# msp430f5528.net
KiCad netlist of a schematic drawn in EAGLE
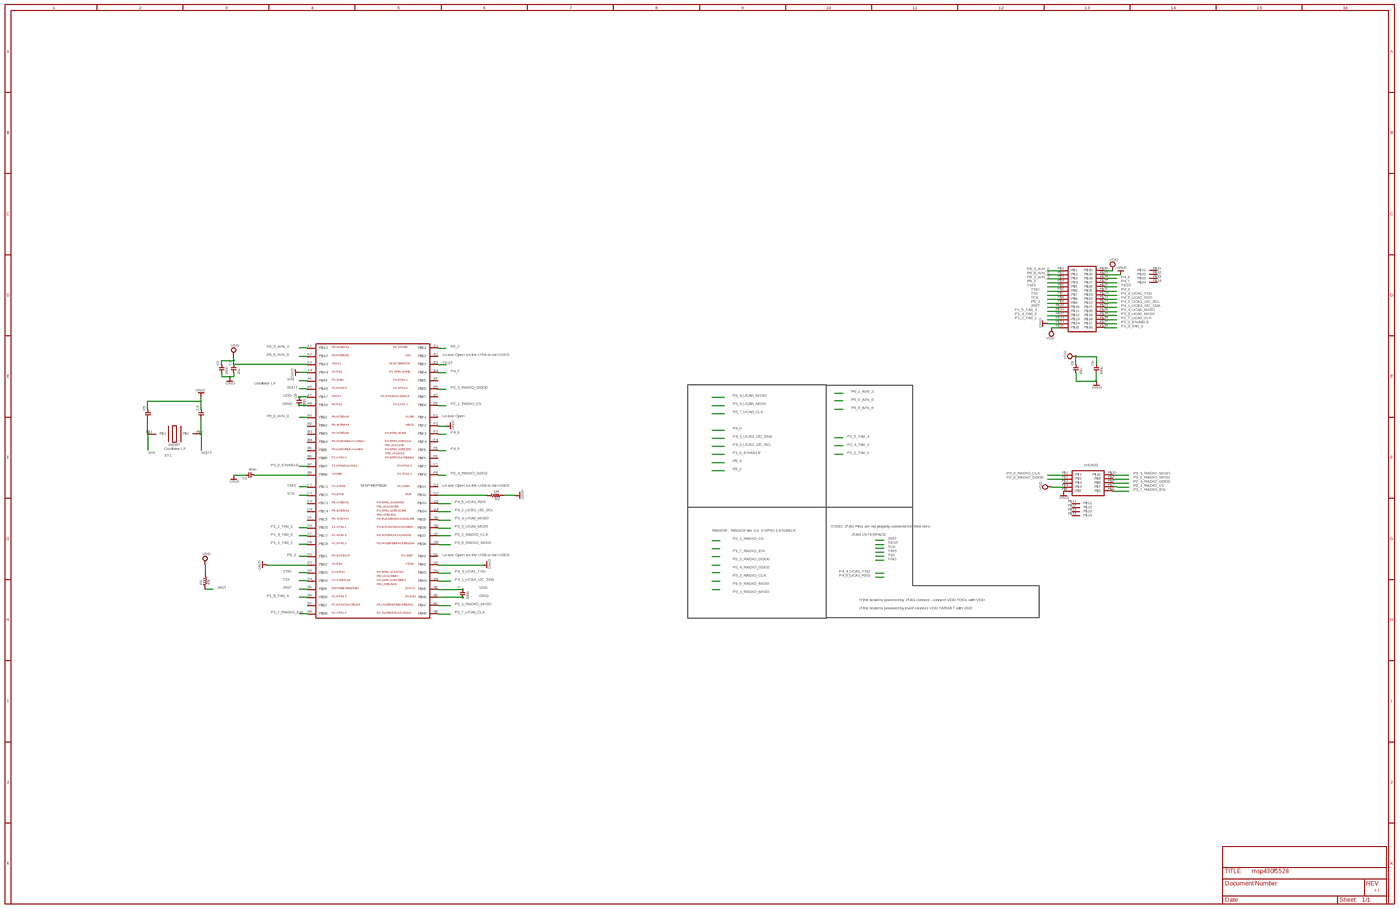
[diagram p0: schematic, sheet 1, overview]
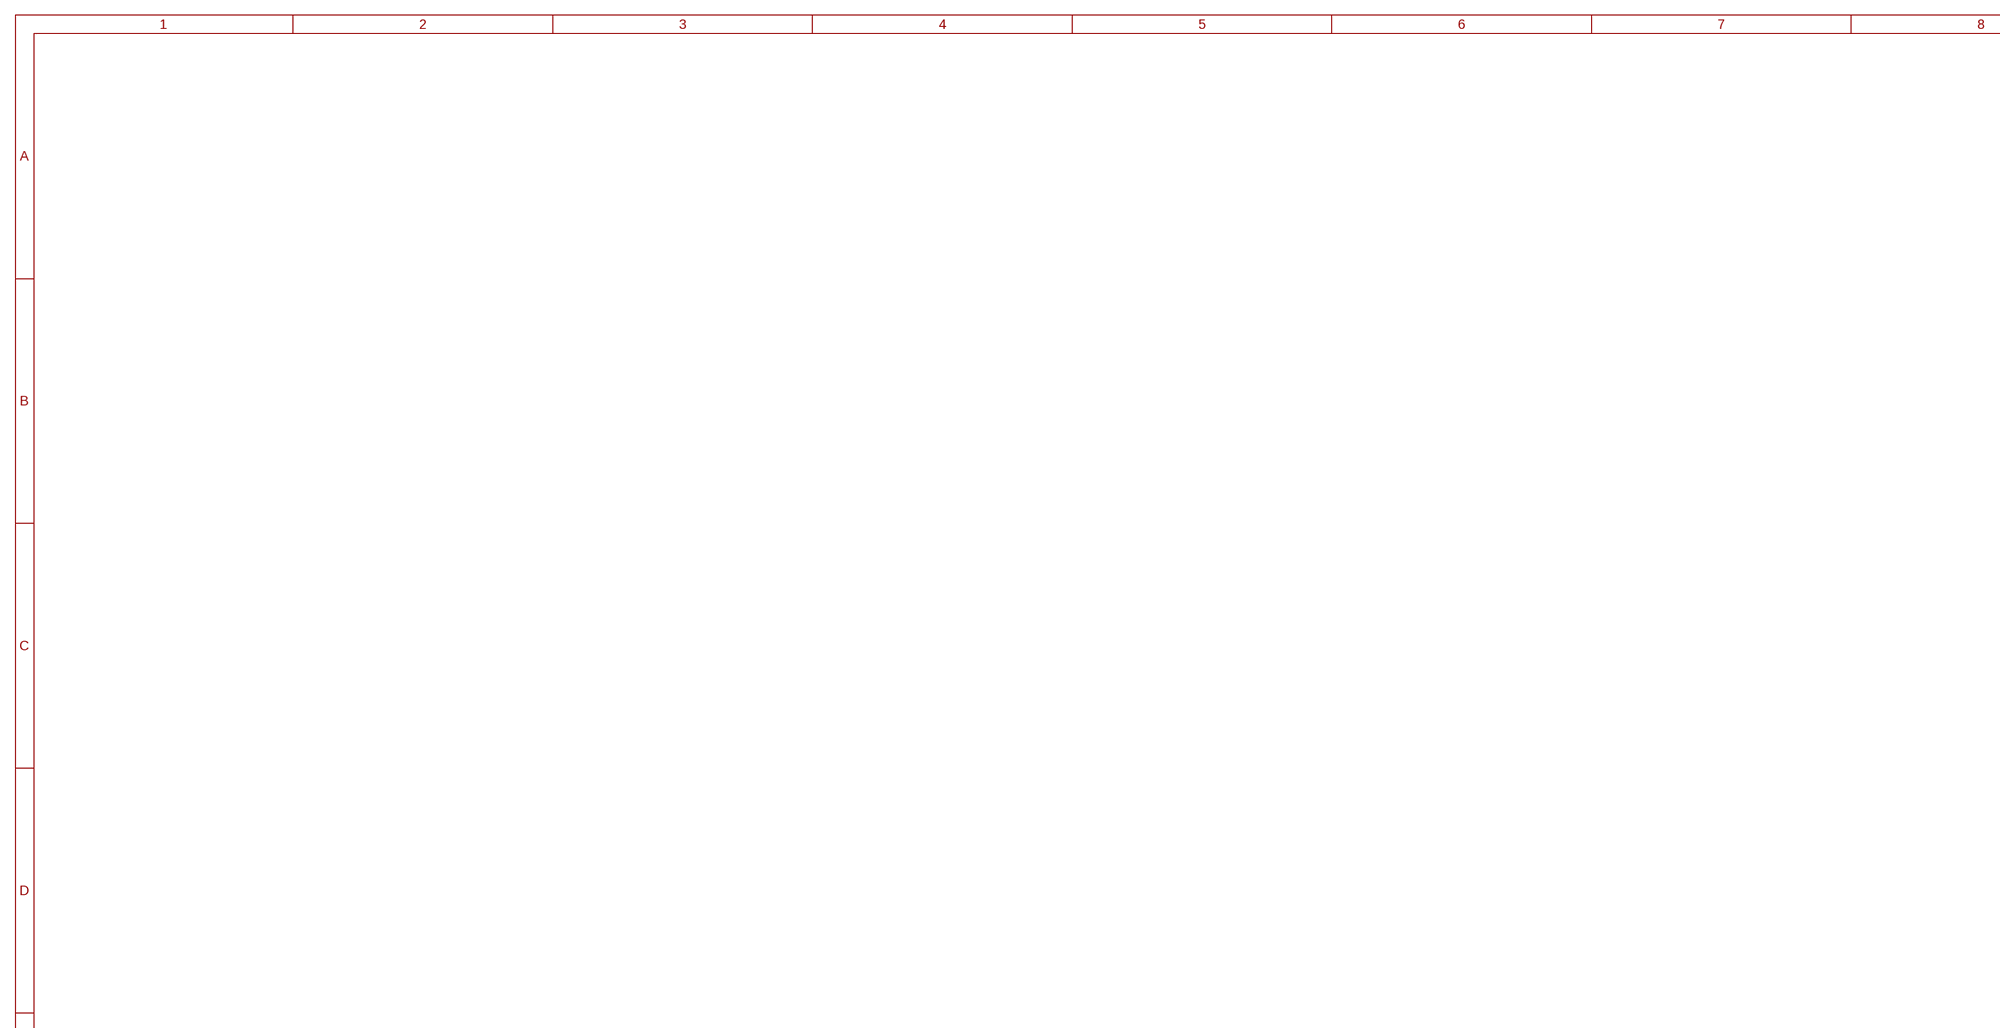
[diagram p1: schematic, sheet 1, part 1 of 4]
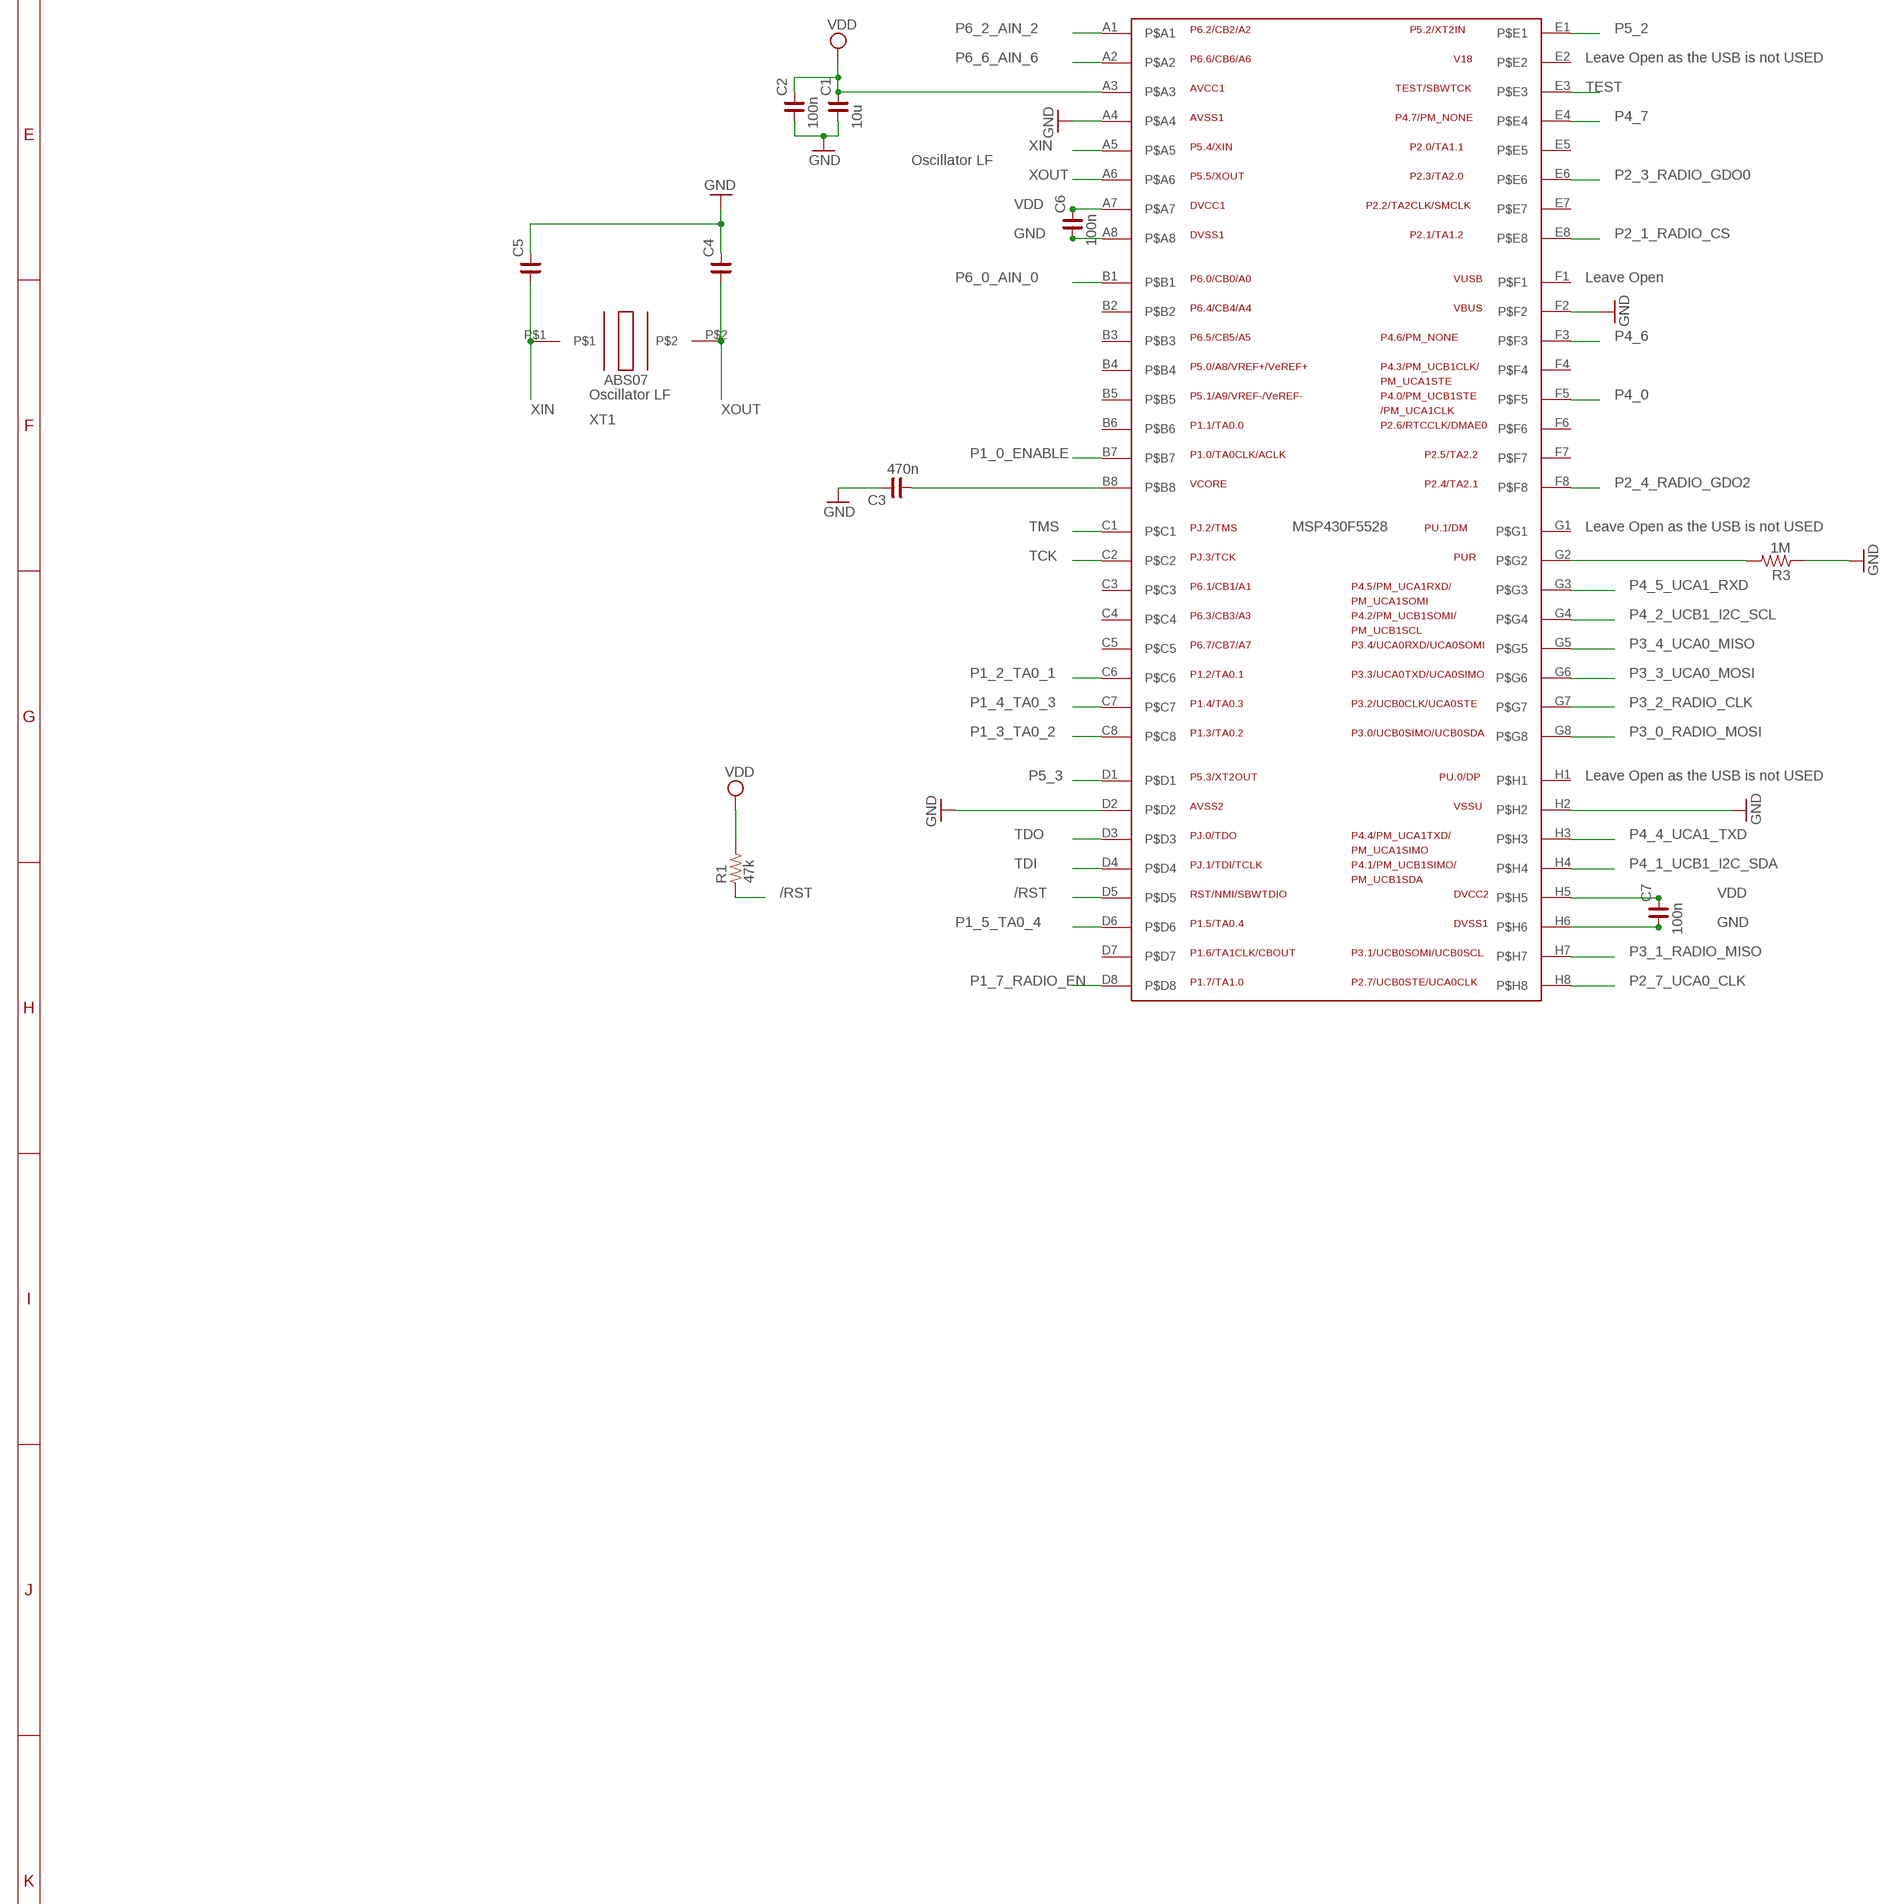
[diagram p2: schematic, sheet 1, part 2 of 4]
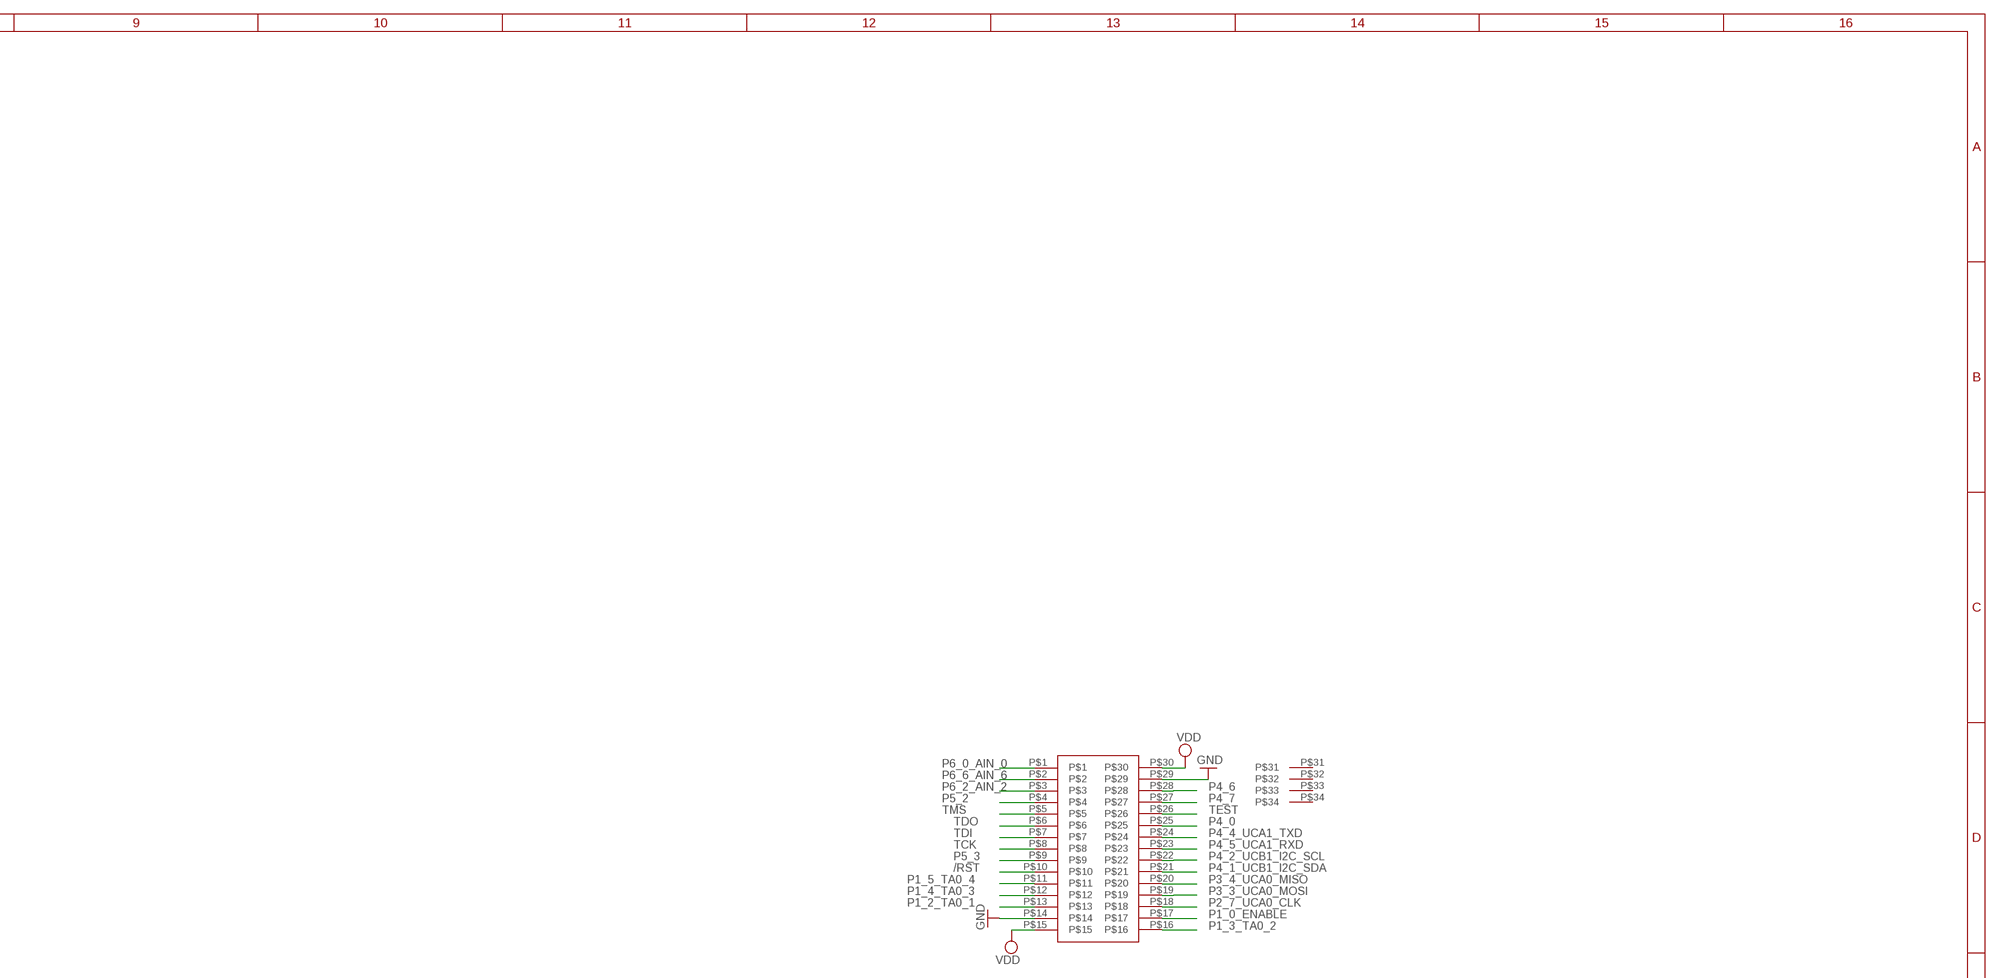
[diagram p3: schematic, sheet 1, part 3 of 4]
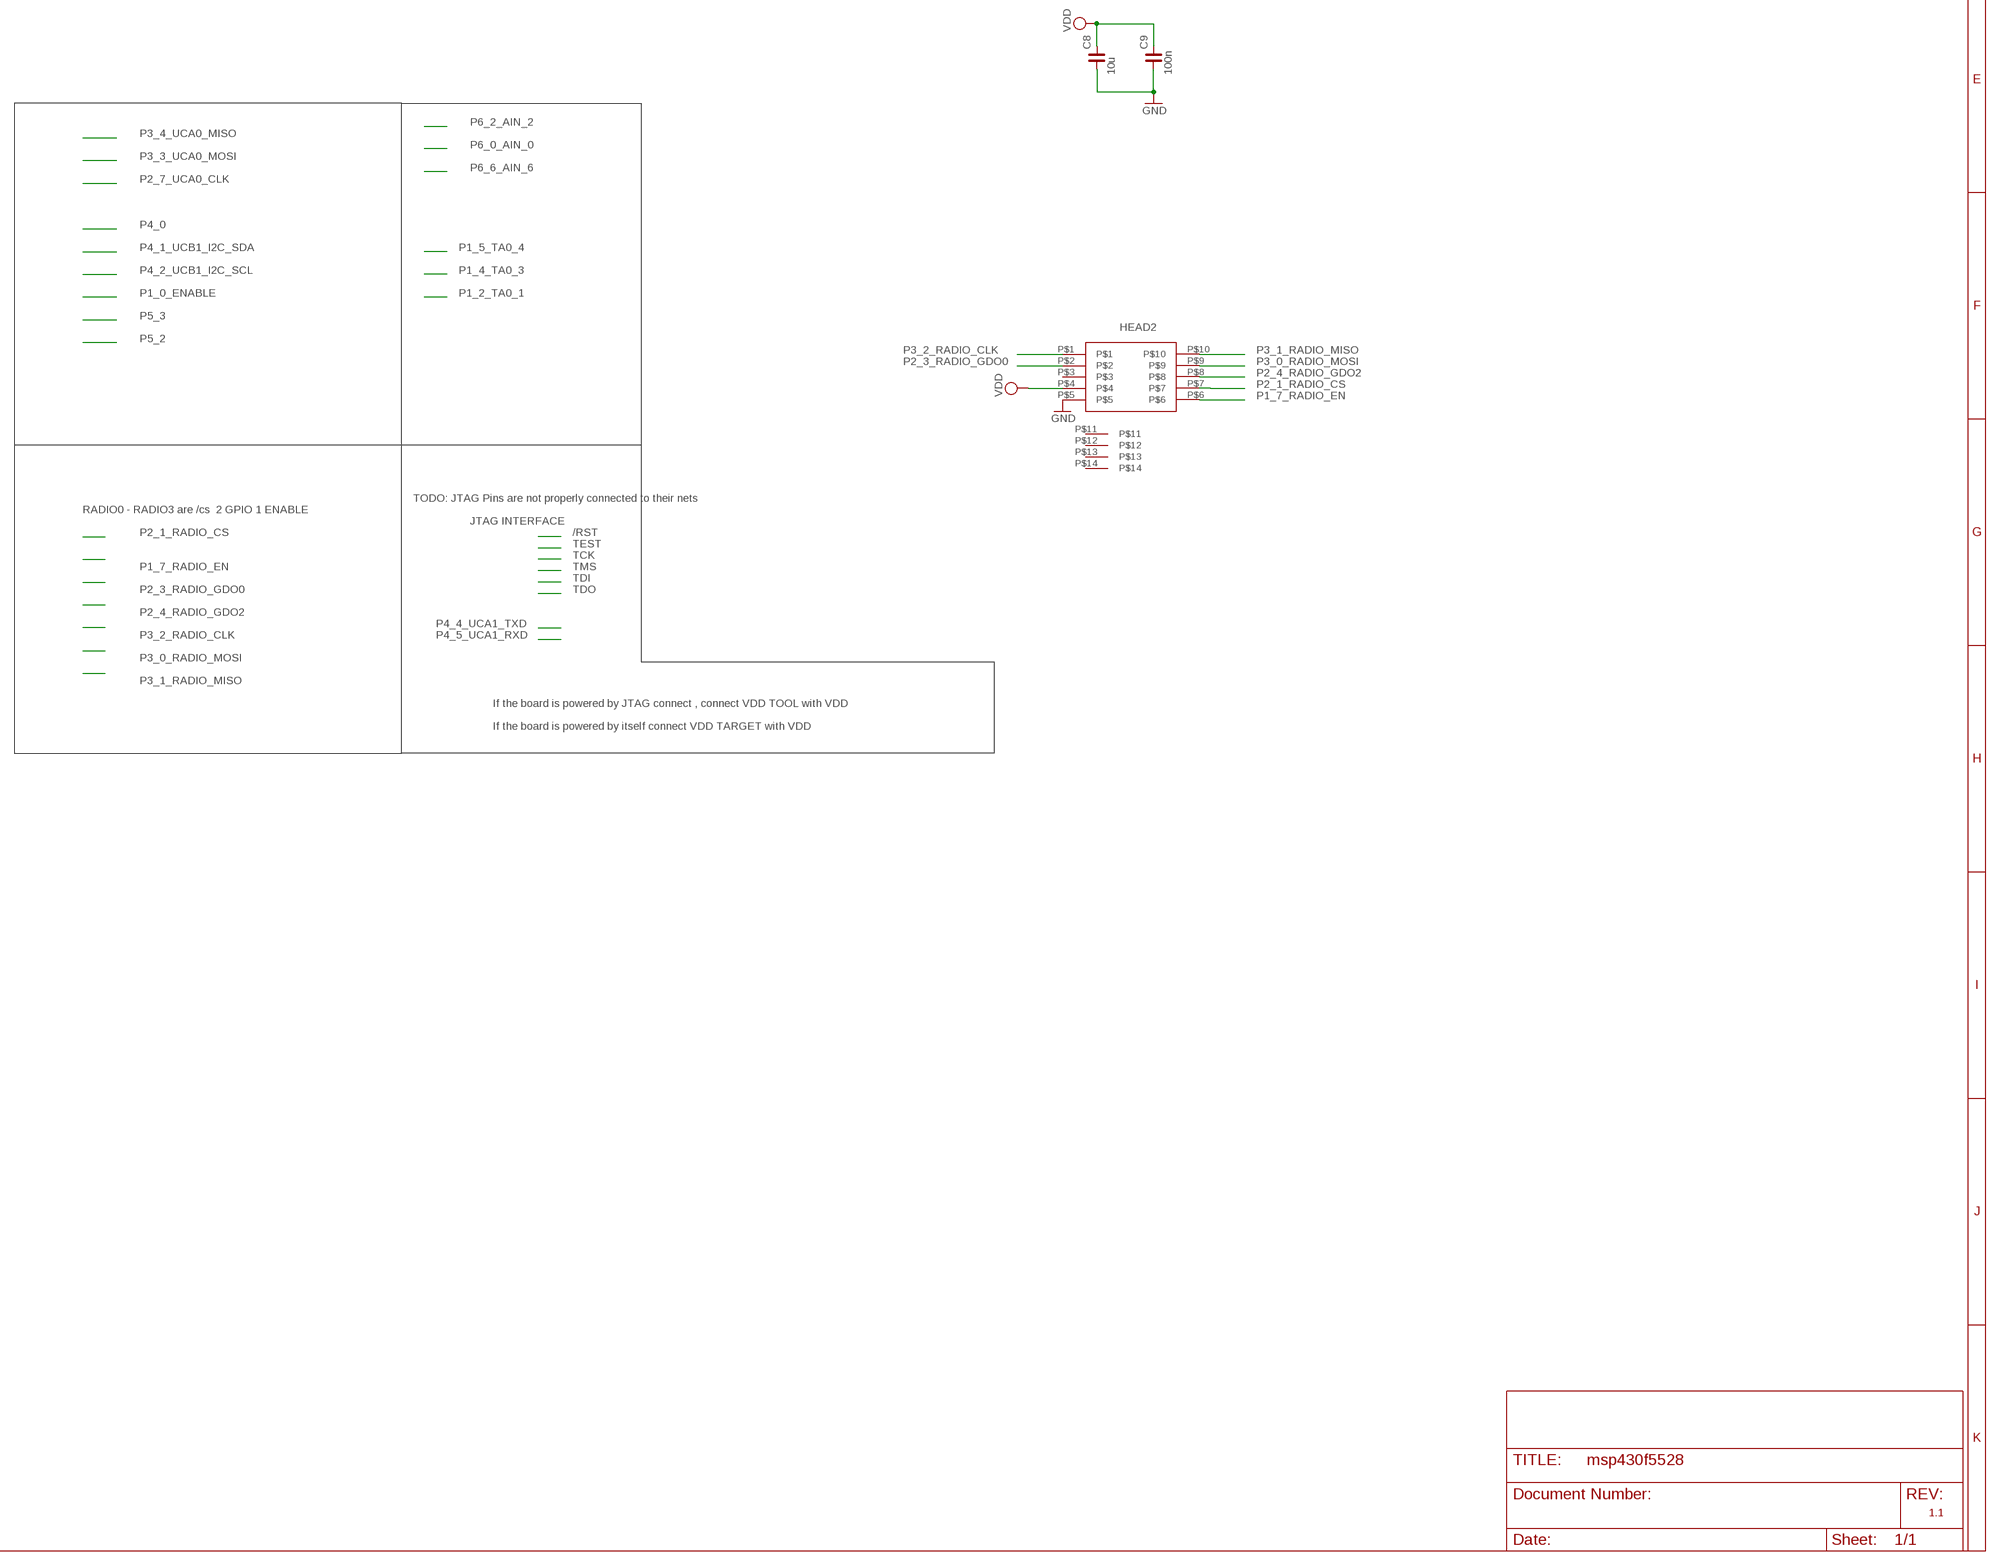
[diagram p4: schematic, sheet 1, part 4 of 4]

(export (version "E")
  (design (tool "Eeschema 10.0.6"))
  (components
    (comp (ref "C1")
      (value "10u")
      (footprint "eagle-import:C0402")
      (libsource (lib "eagle-import") (part "C_0402"))
    )
    (comp (ref "C2")
      (value "100n")
      (footprint "eagle-import:C0402")
      (libsource (lib "eagle-import") (part "C_0402"))
    )
    (comp (ref "C3")
      (value "470n")
      (footprint "eagle-import:C0402")
      (libsource (lib "eagle-import") (part "C_0402"))
    )
    (comp (ref "C4")
      (value "C_0402")
      (footprint "eagle-import:C0402")
      (libsource (lib "eagle-import") (part "C_0402"))
    )
    (comp (ref "C5")
      (value "C_0402")
      (footprint "eagle-import:C0402")
      (libsource (lib "eagle-import") (part "C_0402"))
    )
    (comp (ref "C6")
      (value "100n")
      (footprint "eagle-import:C0402")
      (libsource (lib "eagle-import") (part "C_0402"))
    )
    (comp (ref "C7")
      (value "100n")
      (footprint "eagle-import:C0402")
      (libsource (lib "eagle-import") (part "C_0402"))
    )
    (comp (ref "C8")
      (value "10u")
      (footprint "eagle-import:C0402")
      (libsource (lib "eagle-import") (part "C_0402"))
    )
    (comp (ref "C9")
      (value "100n")
      (footprint "eagle-import:C0402")
      (libsource (lib "eagle-import") (part "C_0402"))
    )
    (comp (ref "R1")
      (value "47k")
      (footprint "eagle-import:R0402")
      (libsource (lib "eagle-import") (part "R_0402"))
    )
    (comp (ref "R3")
      (value "1M")
      (footprint "eagle-import:R0402")
      (libsource (lib "eagle-import") (part "R_0402"))
    )
    (comp (ref "U$1")
      (value "MSP430F5528")
      (footprint "eagle-import:YFF64")
      (libsource (lib "eagle-import") (part "MSP430F5528"))
    )
    (comp (ref "U$2")
      (value "OSC32K")
      (footprint "eagle-import:ABS07")
      (fields (field (name "PARTNUMBER") "5359801-ND"))
      (libsource (lib "eagle-import") (part "OSC32K"))
    )
    (comp (ref "U$4")
      (value "55909-0374_PLUG")
      (footprint "eagle-import:55909-0374_PLUG")
      (libsource (lib "eagle-import") (part "55909-0374_PLUG"))
    )
    (comp (ref "U$5")
      (value "559099872_2X5_PLUG")
      (footprint "eagle-import:559099872_2X5_PLUG")
      (libsource (lib "eagle-import") (part "559099872_2X5_PLUG"))
    )
  )
  (nets
    (net (code "1") (name "/P1_0_ENABLE") (class "Default")
      (node (ref "U$1") (pin "B7") (pinfunction "P$B7_B7") (pintype "bidirectional"))
      (node (ref "U$4") (pin "P$17") (pinfunction "P$17_P$17") (pintype "bidirectional"))
    )
    (net (code "2") (name "/P1_2_TA0_1") (class "Default")
      (node (ref "U$1") (pin "C6") (pinfunction "P$C6_C6") (pintype "bidirectional"))
      (node (ref "U$4") (pin "P$13") (pinfunction "P$13_P$13") (pintype "bidirectional"))
    )
    (net (code "3") (name "/P1_3_TA0_2") (class "Default")
      (node (ref "U$1") (pin "C8") (pinfunction "P$C8_C8") (pintype "bidirectional"))
      (node (ref "U$4") (pin "P$16") (pinfunction "P$16_P$16") (pintype "bidirectional"))
    )
    (net (code "4") (name "/P1_4_TA0_3") (class "Default")
      (node (ref "U$1") (pin "C7") (pinfunction "P$C7_C7") (pintype "bidirectional"))
      (node (ref "U$4") (pin "P$12") (pinfunction "P$12_P$12") (pintype "bidirectional"))
    )
    (net (code "5") (name "/P1_5_TA0_4") (class "Default")
      (node (ref "U$1") (pin "D6") (pinfunction "P$D6_D6") (pintype "bidirectional"))
      (node (ref "U$4") (pin "P$11") (pinfunction "P$11_P$11") (pintype "bidirectional"))
    )
    (net (code "6") (name "/P1_7_RADIO_EN") (class "Default")
      (node (ref "U$1") (pin "D8") (pinfunction "P$D8_D8") (pintype "bidirectional"))
      (node (ref "U$5") (pin "P$6") (pinfunction "P$6_P$6") (pintype "bidirectional"))
    )
    (net (code "7") (name "/P2_1_RADIO_CS") (class "Default")
      (node (ref "U$1") (pin "E8") (pinfunction "P$E8_E8") (pintype "bidirectional"))
      (node (ref "U$5") (pin "P$7") (pinfunction "P$7_P$7") (pintype "bidirectional"))
    )
    (net (code "8") (name "/P2_3_RADIO_GDO0") (class "Default")
      (node (ref "U$1") (pin "E6") (pinfunction "P$E6_E6") (pintype "bidirectional"))
      (node (ref "U$5") (pin "P$2") (pinfunction "P$2_P$2") (pintype "bidirectional"))
    )
    (net (code "9") (name "/P2_4_RADIO_GDO2") (class "Default")
      (node (ref "U$1") (pin "F8") (pinfunction "P$F8_F8") (pintype "bidirectional"))
      (node (ref "U$5") (pin "P$8") (pinfunction "P$8_P$8") (pintype "bidirectional"))
    )
    (net (code "10") (name "/P2_7_UCA0_CLK") (class "Default")
      (node (ref "U$1") (pin "H8") (pinfunction "P$H8_H8") (pintype "bidirectional"))
      (node (ref "U$4") (pin "P$18") (pinfunction "P$18_P$18") (pintype "bidirectional"))
    )
    (net (code "11") (name "/P3_0_RADIO_MOSI") (class "Default")
      (node (ref "U$1") (pin "G8") (pinfunction "P$G8_G8") (pintype "bidirectional"))
      (node (ref "U$5") (pin "P$9") (pinfunction "P$9_P$9") (pintype "bidirectional"))
    )
    (net (code "12") (name "/P3_1_RADIO_MISO") (class "Default")
      (node (ref "U$1") (pin "H7") (pinfunction "P$H7_H7") (pintype "bidirectional"))
      (node (ref "U$5") (pin "P$10") (pinfunction "P$10_P$10") (pintype "bidirectional"))
    )
    (net (code "13") (name "/P3_2_RADIO_CLK") (class "Default")
      (node (ref "U$1") (pin "G7") (pinfunction "P$G7_G7") (pintype "bidirectional"))
      (node (ref "U$5") (pin "P$1") (pinfunction "P$1_P$1") (pintype "bidirectional"))
    )
    (net (code "14") (name "/P3_3_UCA0_MOSI") (class "Default")
      (node (ref "U$1") (pin "G6") (pinfunction "P$G6_G6") (pintype "bidirectional"))
      (node (ref "U$4") (pin "P$19") (pinfunction "P$19_P$19") (pintype "bidirectional"))
    )
    (net (code "15") (name "/P3_4_UCA0_MISO") (class "Default")
      (node (ref "U$1") (pin "G5") (pinfunction "P$G5_G5") (pintype "bidirectional"))
      (node (ref "U$4") (pin "P$20") (pinfunction "P$20_P$20") (pintype "bidirectional"))
    )
    (net (code "16") (name "/P4_0") (class "Default")
      (node (ref "U$1") (pin "F5") (pinfunction "P$F5_F5") (pintype "bidirectional"))
      (node (ref "U$4") (pin "P$25") (pinfunction "P$25_P$25") (pintype "bidirectional"))
    )
    (net (code "17") (name "/P4_1_UCB1_I2C_SDA") (class "Default")
      (node (ref "U$1") (pin "H4") (pinfunction "P$H4_H4") (pintype "bidirectional"))
      (node (ref "U$4") (pin "P$21") (pinfunction "P$21_P$21") (pintype "bidirectional"))
    )
    (net (code "18") (name "/P4_2_UCB1_I2C_SCL") (class "Default")
      (node (ref "U$1") (pin "G4") (pinfunction "P$G4_G4") (pintype "bidirectional"))
      (node (ref "U$4") (pin "P$22") (pinfunction "P$22_P$22") (pintype "bidirectional"))
    )
    (net (code "19") (name "/P4_4_UCA1_TXD") (class "Default")
      (node (ref "U$1") (pin "H3") (pinfunction "P$H3_H3") (pintype "bidirectional"))
      (node (ref "U$4") (pin "P$24") (pinfunction "P$24_P$24") (pintype "bidirectional"))
    )
    (net (code "20") (name "/P4_5_UCA1_RXD") (class "Default")
      (node (ref "U$1") (pin "G3") (pinfunction "P$G3_G3") (pintype "bidirectional"))
      (node (ref "U$4") (pin "P$23") (pinfunction "P$23_P$23") (pintype "bidirectional"))
    )
    (net (code "21") (name "/P4_6") (class "Default")
      (node (ref "U$1") (pin "F3") (pinfunction "P$F3_F3") (pintype "bidirectional"))
      (node (ref "U$4") (pin "P$28") (pinfunction "P$28_P$28") (pintype "bidirectional"))
    )
    (net (code "22") (name "/P4_7") (class "Default")
      (node (ref "U$1") (pin "E4") (pinfunction "P$E4_E4") (pintype "bidirectional"))
      (node (ref "U$4") (pin "P$27") (pinfunction "P$27_P$27") (pintype "bidirectional"))
    )
    (net (code "23") (name "/P5_2") (class "Default")
      (node (ref "U$1") (pin "E1") (pinfunction "P$E1_E1") (pintype "bidirectional"))
      (node (ref "U$4") (pin "P$4") (pinfunction "P$4_P$4") (pintype "bidirectional"))
    )
    (net (code "24") (name "/P5_3") (class "Default")
      (node (ref "U$1") (pin "D1") (pinfunction "P$D1_D1") (pintype "bidirectional"))
      (node (ref "U$4") (pin "P$9") (pinfunction "P$9_P$9") (pintype "bidirectional"))
    )
    (net (code "25") (name "/P6_0_AIN_0") (class "Default")
      (node (ref "U$1") (pin "B1") (pinfunction "P$B1_B1") (pintype "bidirectional"))
      (node (ref "U$4") (pin "P$1") (pinfunction "P$1_P$1") (pintype "bidirectional"))
    )
    (net (code "26") (name "/P6_2_AIN_2") (class "Default")
      (node (ref "U$1") (pin "A1") (pinfunction "P$A1_A1") (pintype "bidirectional"))
      (node (ref "U$4") (pin "P$3") (pinfunction "P$3_P$3") (pintype "bidirectional"))
    )
    (net (code "27") (name "/P6_6_AIN_6") (class "Default")
      (node (ref "U$1") (pin "A2") (pinfunction "P$A2_A2") (pintype "bidirectional"))
      (node (ref "U$4") (pin "P$2") (pinfunction "P$2_P$2") (pintype "bidirectional"))
    )
    (net (code "28") (name "/TCK") (class "Default")
      (node (ref "U$1") (pin "C2") (pinfunction "P$C2_C2") (pintype "bidirectional"))
      (node (ref "U$4") (pin "P$8") (pinfunction "P$8_P$8") (pintype "bidirectional"))
    )
    (net (code "29") (name "/TDI") (class "Default")
      (node (ref "U$1") (pin "D4") (pinfunction "P$D4_D4") (pintype "bidirectional"))
      (node (ref "U$4") (pin "P$7") (pinfunction "P$7_P$7") (pintype "bidirectional"))
    )
    (net (code "30") (name "/TDO") (class "Default")
      (node (ref "U$1") (pin "D3") (pinfunction "P$D3_D3") (pintype "bidirectional"))
      (node (ref "U$4") (pin "P$6") (pinfunction "P$6_P$6") (pintype "bidirectional"))
    )
    (net (code "31") (name "/TEST") (class "Default")
      (node (ref "U$1") (pin "E3") (pinfunction "P$E3_E3") (pintype "bidirectional"))
      (node (ref "U$4") (pin "P$26") (pinfunction "P$26_P$26") (pintype "bidirectional"))
    )
    (net (code "32") (name "/TMS") (class "Default")
      (node (ref "U$1") (pin "C1") (pinfunction "P$C1_C1") (pintype "bidirectional"))
      (node (ref "U$4") (pin "P$5") (pinfunction "P$5_P$5") (pintype "bidirectional"))
    )
    (net (code "33") (name "/XIN") (class "Default")
      (node (ref "C5") (pin "1") (pinfunction "1_1") (pintype "passive"))
      (node (ref "U$1") (pin "A5") (pinfunction "P$A5_A5") (pintype "bidirectional"))
      (node (ref "U$2") (pin "P$1") (pinfunction "P$1_P$1") (pintype "bidirectional"))
    )
    (net (code "34") (name "/XOUT") (class "Default")
      (node (ref "C4") (pin "1") (pinfunction "1_1") (pintype "passive"))
      (node (ref "U$1") (pin "A6") (pinfunction "P$A6_A6") (pintype "bidirectional"))
      (node (ref "U$2") (pin "P$2") (pinfunction "P$2_P$2") (pintype "bidirectional"))
    )
    (net (code "35") (name "/{slash}RST") (class "Default")
      (node (ref "R1") (pin "1") (pinfunction "1_1") (pintype "passive"))
      (node (ref "U$1") (pin "D5") (pinfunction "P$D5_D5") (pintype "bidirectional"))
      (node (ref "U$4") (pin "P$10") (pinfunction "P$10_P$10") (pintype "bidirectional"))
    )
    (net (code "36") (name "GND") (class "Default")
      (node (ref "C1") (pin "1") (pinfunction "1_1") (pintype "passive"))
      (node (ref "C2") (pin "1") (pinfunction "1_1") (pintype "passive"))
      (node (ref "C3") (pin "2") (pinfunction "2_2") (pintype "passive"))
      (node (ref "C4") (pin "2") (pinfunction "2_2") (pintype "passive"))
      (node (ref "C5") (pin "2") (pinfunction "2_2") (pintype "passive"))
      (node (ref "C6") (pin "1") (pinfunction "1_1") (pintype "passive"))
      (node (ref "C7") (pin "1") (pinfunction "1_1") (pintype "passive"))
      (node (ref "C8") (pin "1") (pinfunction "1_1") (pintype "passive"))
      (node (ref "C9") (pin "1") (pinfunction "1_1") (pintype "passive"))
      (node (ref "R3") (pin "1") (pinfunction "1_1") (pintype "passive"))
      (node (ref "U$1") (pin "A4") (pinfunction "P$A4_A4") (pintype "bidirectional"))
      (node (ref "U$1") (pin "A8") (pinfunction "P$A8_A8") (pintype "bidirectional"))
      (node (ref "U$1") (pin "D2") (pinfunction "P$D2_D2") (pintype "bidirectional"))
      (node (ref "U$1") (pin "F2") (pinfunction "P$F2_F2") (pintype "bidirectional"))
      (node (ref "U$1") (pin "H2") (pinfunction "P$H2_H2") (pintype "bidirectional"))
      (node (ref "U$1") (pin "H6") (pinfunction "P$H6_H6") (pintype "bidirectional"))
      (node (ref "U$4") (pin "P$14") (pinfunction "P$14_P$14") (pintype "bidirectional"))
      (node (ref "U$4") (pin "P$29") (pinfunction "P$29_P$29") (pintype "bidirectional"))
      (node (ref "U$5") (pin "P$5") (pinfunction "P$5_P$5") (pintype "bidirectional"))
    )
    (net (code "37") (name "Net-(U$1-P$B8)") (class "Default")
      (node (ref "C3") (pin "1") (pinfunction "1_1") (pintype "passive"))
      (node (ref "U$1") (pin "B8") (pinfunction "P$B8_B8") (pintype "bidirectional"))
    )
    (net (code "38") (name "Net-(U$1-P$G2)") (class "Default")
      (node (ref "R3") (pin "2") (pinfunction "2_2") (pintype "passive"))
      (node (ref "U$1") (pin "G2") (pinfunction "P$G2_G2") (pintype "bidirectional"))
    )
    (net (code "39") (name "VDD") (class "Default")
      (node (ref "C1") (pin "2") (pinfunction "2_2") (pintype "passive"))
      (node (ref "C2") (pin "2") (pinfunction "2_2") (pintype "passive"))
      (node (ref "C6") (pin "2") (pinfunction "2_2") (pintype "passive"))
      (node (ref "C7") (pin "2") (pinfunction "2_2") (pintype "passive"))
      (node (ref "C8") (pin "2") (pinfunction "2_2") (pintype "passive"))
      (node (ref "C9") (pin "2") (pinfunction "2_2") (pintype "passive"))
      (node (ref "R1") (pin "2") (pinfunction "2_2") (pintype "passive"))
      (node (ref "U$1") (pin "A3") (pinfunction "P$A3_A3") (pintype "bidirectional"))
      (node (ref "U$1") (pin "A7") (pinfunction "P$A7_A7") (pintype "bidirectional"))
      (node (ref "U$1") (pin "H5") (pinfunction "P$H5_H5") (pintype "bidirectional"))
      (node (ref "U$4") (pin "P$15") (pinfunction "P$15_P$15") (pintype "bidirectional"))
      (node (ref "U$4") (pin "P$30") (pinfunction "P$30_P$30") (pintype "bidirectional"))
      (node (ref "U$5") (pin "P$4") (pinfunction "P$4_P$4") (pintype "bidirectional"))
    )
    (net (code "40") (name "unconnected-(U$1-P$B2-PadB2)") (class "Default")
      (node (ref "U$1") (pin "B2") (pinfunction "P$B2_B2") (pintype "bidirectional"))
    )
    (net (code "41") (name "unconnected-(U$1-P$B3-PadB3)") (class "Default")
      (node (ref "U$1") (pin "B3") (pinfunction "P$B3_B3") (pintype "bidirectional"))
    )
    (net (code "42") (name "unconnected-(U$1-P$B4-PadB4)") (class "Default")
      (node (ref "U$1") (pin "B4") (pinfunction "P$B4_B4") (pintype "bidirectional"))
    )
    (net (code "43") (name "unconnected-(U$1-P$B5-PadB5)") (class "Default")
      (node (ref "U$1") (pin "B5") (pinfunction "P$B5_B5") (pintype "bidirectional"))
    )
    (net (code "44") (name "unconnected-(U$1-P$B6-PadB6)") (class "Default")
      (node (ref "U$1") (pin "B6") (pinfunction "P$B6_B6") (pintype "bidirectional"))
    )
    (net (code "45") (name "unconnected-(U$1-P$C3-PadC3)") (class "Default")
      (node (ref "U$1") (pin "C3") (pinfunction "P$C3_C3") (pintype "bidirectional"))
    )
    (net (code "46") (name "unconnected-(U$1-P$C4-PadC4)") (class "Default")
      (node (ref "U$1") (pin "C4") (pinfunction "P$C4_C4") (pintype "bidirectional"))
    )
    (net (code "47") (name "unconnected-(U$1-P$C5-PadC5)") (class "Default")
      (node (ref "U$1") (pin "C5") (pinfunction "P$C5_C5") (pintype "bidirectional"))
    )
    (net (code "48") (name "unconnected-(U$1-P$D7-PadD7)") (class "Default")
      (node (ref "U$1") (pin "D7") (pinfunction "P$D7_D7") (pintype "bidirectional"))
    )
    (net (code "49") (name "unconnected-(U$1-P$E2-PadE2)") (class "Default")
      (node (ref "U$1") (pin "E2") (pinfunction "P$E2_E2") (pintype "bidirectional"))
    )
    (net (code "50") (name "unconnected-(U$1-P$E5-PadE5)") (class "Default")
      (node (ref "U$1") (pin "E5") (pinfunction "P$E5_E5") (pintype "bidirectional"))
    )
    (net (code "51") (name "unconnected-(U$1-P$E7-PadE7)") (class "Default")
      (node (ref "U$1") (pin "E7") (pinfunction "P$E7_E7") (pintype "bidirectional"))
    )
    (net (code "52") (name "unconnected-(U$1-P$F1-PadF1)") (class "Default")
      (node (ref "U$1") (pin "F1") (pinfunction "P$F1_F1") (pintype "bidirectional"))
    )
    (net (code "53") (name "unconnected-(U$1-P$F4-PadF4)") (class "Default")
      (node (ref "U$1") (pin "F4") (pinfunction "P$F4_F4") (pintype "bidirectional"))
    )
    (net (code "54") (name "unconnected-(U$1-P$F6-PadF6)") (class "Default")
      (node (ref "U$1") (pin "F6") (pinfunction "P$F6_F6") (pintype "bidirectional"))
    )
    (net (code "55") (name "unconnected-(U$1-P$F7-PadF7)") (class "Default")
      (node (ref "U$1") (pin "F7") (pinfunction "P$F7_F7") (pintype "bidirectional"))
    )
    (net (code "56") (name "unconnected-(U$1-P$G1-PadG1)") (class "Default")
      (node (ref "U$1") (pin "G1") (pinfunction "P$G1_G1") (pintype "bidirectional"))
    )
    (net (code "57") (name "unconnected-(U$1-P$H1-PadH1)") (class "Default")
      (node (ref "U$1") (pin "H1") (pinfunction "P$H1_H1") (pintype "bidirectional"))
    )
    (net (code "58") (name "unconnected-(U$4-PadP$31)") (class "Default")
      (node (ref "U$4") (pin "P$31") (pinfunction "P$31_P$31") (pintype "bidirectional"))
    )
    (net (code "59") (name "unconnected-(U$4-PadP$32)") (class "Default")
      (node (ref "U$4") (pin "P$32") (pinfunction "P$32_P$32") (pintype "bidirectional"))
    )
    (net (code "60") (name "unconnected-(U$4-PadP$33)") (class "Default")
      (node (ref "U$4") (pin "P$33") (pinfunction "P$33_P$33") (pintype "bidirectional"))
    )
    (net (code "61") (name "unconnected-(U$4-PadP$34)") (class "Default")
      (node (ref "U$4") (pin "P$34") (pinfunction "P$34_P$34") (pintype "bidirectional"))
    )
    (net (code "62") (name "unconnected-(U$5-PadP$3)") (class "Default")
      (node (ref "U$5") (pin "P$3") (pinfunction "P$3_P$3") (pintype "bidirectional"))
    )
    (net (code "63") (name "unconnected-(U$5-PadP$11)") (class "Default")
      (node (ref "U$5") (pin "P$11") (pinfunction "P$11_P$11") (pintype "bidirectional"))
    )
    (net (code "64") (name "unconnected-(U$5-PadP$12)") (class "Default")
      (node (ref "U$5") (pin "P$12") (pinfunction "P$12_P$12") (pintype "bidirectional"))
    )
    (net (code "65") (name "unconnected-(U$5-PadP$13)") (class "Default")
      (node (ref "U$5") (pin "P$13") (pinfunction "P$13_P$13") (pintype "bidirectional"))
    )
    (net (code "66") (name "unconnected-(U$5-PadP$14)") (class "Default")
      (node (ref "U$5") (pin "P$14") (pinfunction "P$14_P$14") (pintype "bidirectional"))
    )
  )
)
